# programmer.net
KiCad netlist of a schematic drawn in EAGLE
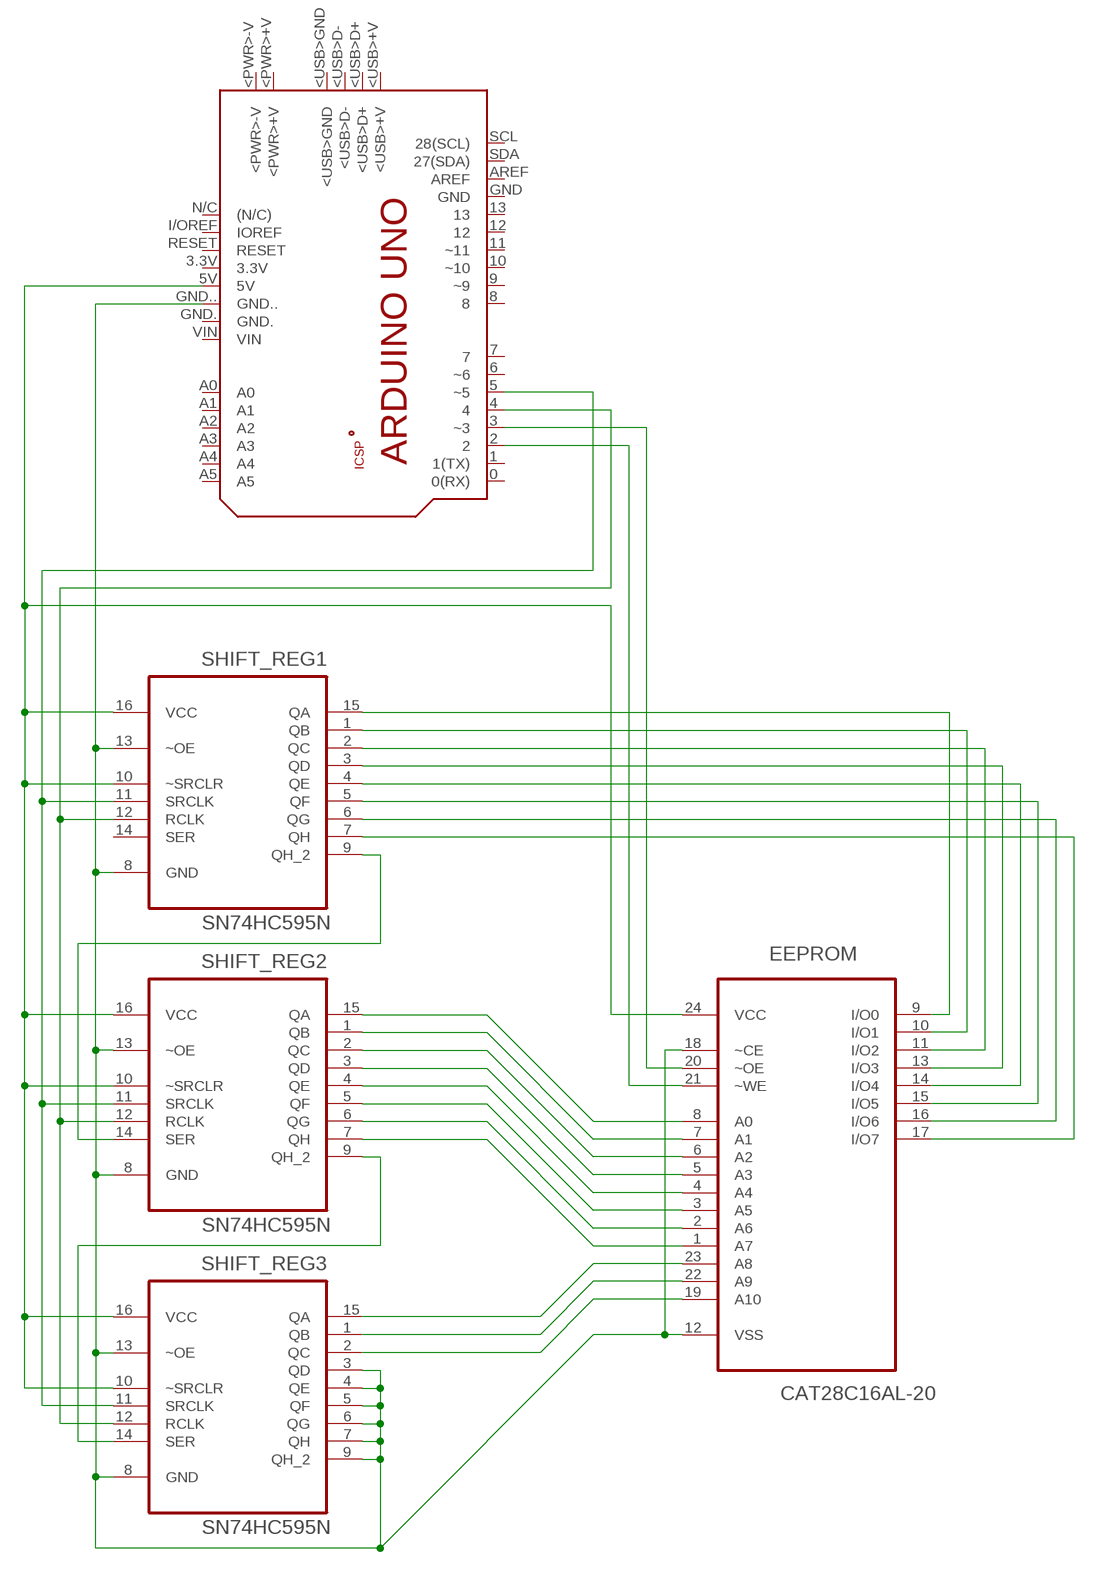
[diagram p0: schematic, sheet 1]

(export (version "E")
  (design (tool "Eeschema 10.0.6"))
  (components
    (comp (ref "EEPROM")
      (value "CAT28C16AL-20")
      (footprint "eagle-import:DIP254P1524X635-24")
      (libsource (lib "eagle-import") (part "CAT28C16AL-20"))
    )
    (comp (ref "MCU")
      (value "ARDUINO_UNO")
      (footprint "eagle-import:ARDUINO_UNO")
      (libsource (lib "eagle-import") (part "ARDUINO_UNO"))
    )
    (comp (ref "SHIFT_REG1")
      (value "SN74HC595N")
      (footprint "eagle-import:DIP254P762X508-16")
      (libsource (lib "eagle-import") (part "SN74HC595N"))
    )
    (comp (ref "SHIFT_REG2")
      (value "SN74HC595N")
      (footprint "eagle-import:DIP254P762X508-16")
      (libsource (lib "eagle-import") (part "SN74HC595N"))
    )
    (comp (ref "SHIFT_REG3")
      (value "SN74HC595N")
      (footprint "eagle-import:DIP254P762X508-16")
      (libsource (lib "eagle-import") (part "SN74HC595N"))
    )
  )
  (nets
    (net (code "1") (name "Net-(EEPROM-A0)") (class "Default")
      (node (ref "EEPROM") (pin "8") (pinfunction "A0_8") (pintype "input"))
      (node (ref "SHIFT_REG2") (pin "15") (pinfunction "QA_15") (pintype "output"))
    )
    (net (code "2") (name "Net-(EEPROM-A1)") (class "Default")
      (node (ref "EEPROM") (pin "7") (pinfunction "A1_7") (pintype "input"))
      (node (ref "SHIFT_REG2") (pin "1") (pinfunction "QB_1") (pintype "output"))
    )
    (net (code "3") (name "Net-(EEPROM-A2)") (class "Default")
      (node (ref "EEPROM") (pin "6") (pinfunction "A2_6") (pintype "input"))
      (node (ref "SHIFT_REG2") (pin "2") (pinfunction "QC_2") (pintype "output"))
    )
    (net (code "4") (name "Net-(EEPROM-A3)") (class "Default")
      (node (ref "EEPROM") (pin "5") (pinfunction "A3_5") (pintype "input"))
      (node (ref "SHIFT_REG2") (pin "3") (pinfunction "QD_3") (pintype "output"))
    )
    (net (code "5") (name "Net-(EEPROM-A4)") (class "Default")
      (node (ref "EEPROM") (pin "4") (pinfunction "A4_4") (pintype "input"))
      (node (ref "SHIFT_REG2") (pin "4") (pinfunction "QE_4") (pintype "output"))
    )
    (net (code "6") (name "Net-(EEPROM-A5)") (class "Default")
      (node (ref "EEPROM") (pin "3") (pinfunction "A5_3") (pintype "input"))
      (node (ref "SHIFT_REG2") (pin "5") (pinfunction "QF_5") (pintype "output"))
    )
    (net (code "7") (name "Net-(EEPROM-A6)") (class "Default")
      (node (ref "EEPROM") (pin "2") (pinfunction "A6_2") (pintype "input"))
      (node (ref "SHIFT_REG2") (pin "6") (pinfunction "QG_6") (pintype "output"))
    )
    (net (code "8") (name "Net-(EEPROM-A7)") (class "Default")
      (node (ref "EEPROM") (pin "1") (pinfunction "A7_1") (pintype "input"))
      (node (ref "SHIFT_REG2") (pin "7") (pinfunction "QH_7") (pintype "output"))
    )
    (net (code "9") (name "Net-(EEPROM-A8)") (class "Default")
      (node (ref "EEPROM") (pin "23") (pinfunction "A8_23") (pintype "input"))
      (node (ref "SHIFT_REG3") (pin "15") (pinfunction "QA_15") (pintype "output"))
    )
    (net (code "10") (name "Net-(EEPROM-A9)") (class "Default")
      (node (ref "EEPROM") (pin "22") (pinfunction "A9_22") (pintype "input"))
      (node (ref "SHIFT_REG3") (pin "1") (pinfunction "QB_1") (pintype "output"))
    )
    (net (code "11") (name "Net-(EEPROM-A10)") (class "Default")
      (node (ref "EEPROM") (pin "19") (pinfunction "A10_19") (pintype "input"))
      (node (ref "SHIFT_REG3") (pin "2") (pinfunction "QC_2") (pintype "output"))
    )
    (net (code "12") (name "Net-(EEPROM-I{slash}O0)") (class "Default")
      (node (ref "EEPROM") (pin "9") (pinfunction "I/O0_9") (pintype "bidirectional"))
      (node (ref "SHIFT_REG1") (pin "15") (pinfunction "QA_15") (pintype "output"))
    )
    (net (code "13") (name "Net-(EEPROM-I{slash}O1)") (class "Default")
      (node (ref "EEPROM") (pin "10") (pinfunction "I/O1_10") (pintype "bidirectional"))
      (node (ref "SHIFT_REG1") (pin "1") (pinfunction "QB_1") (pintype "output"))
    )
    (net (code "14") (name "Net-(EEPROM-I{slash}O2)") (class "Default")
      (node (ref "EEPROM") (pin "11") (pinfunction "I/O2_11") (pintype "bidirectional"))
      (node (ref "SHIFT_REG1") (pin "2") (pinfunction "QC_2") (pintype "output"))
    )
    (net (code "15") (name "Net-(EEPROM-I{slash}O3)") (class "Default")
      (node (ref "EEPROM") (pin "13") (pinfunction "I/O3_13") (pintype "bidirectional"))
      (node (ref "SHIFT_REG1") (pin "3") (pinfunction "QD_3") (pintype "output"))
    )
    (net (code "16") (name "Net-(EEPROM-I{slash}O4)") (class "Default")
      (node (ref "EEPROM") (pin "14") (pinfunction "I/O4_14") (pintype "bidirectional"))
      (node (ref "SHIFT_REG1") (pin "4") (pinfunction "QE_4") (pintype "output"))
    )
    (net (code "17") (name "Net-(EEPROM-I{slash}O5)") (class "Default")
      (node (ref "EEPROM") (pin "15") (pinfunction "I/O5_15") (pintype "bidirectional"))
      (node (ref "SHIFT_REG1") (pin "5") (pinfunction "QF_5") (pintype "output"))
    )
    (net (code "18") (name "Net-(EEPROM-I{slash}O6)") (class "Default")
      (node (ref "EEPROM") (pin "16") (pinfunction "I/O6_16") (pintype "bidirectional"))
      (node (ref "SHIFT_REG1") (pin "6") (pinfunction "QG_6") (pintype "output"))
    )
    (net (code "19") (name "Net-(EEPROM-I{slash}O7)") (class "Default")
      (node (ref "EEPROM") (pin "17") (pinfunction "I/O7_17") (pintype "bidirectional"))
      (node (ref "SHIFT_REG1") (pin "7") (pinfunction "QH_7") (pintype "output"))
    )
    (net (code "20") (name "Net-(EEPROM-VCC)") (class "Default")
      (node (ref "EEPROM") (pin "24") (pinfunction "VCC_24") (pintype "power_in"))
      (node (ref "MCU") (pin "5V") (pinfunction "5V_5V") (pintype "bidirectional"))
      (node (ref "SHIFT_REG1") (pin "10") (pinfunction "~{SRCLR}_10") (pintype "input"))
      (node (ref "SHIFT_REG1") (pin "16") (pinfunction "VCC_16") (pintype "power_in"))
      (node (ref "SHIFT_REG2") (pin "10") (pinfunction "~{SRCLR}_10") (pintype "input"))
      (node (ref "SHIFT_REG2") (pin "16") (pinfunction "VCC_16") (pintype "power_in"))
      (node (ref "SHIFT_REG3") (pin "10") (pinfunction "~{SRCLR}_10") (pintype "input"))
      (node (ref "SHIFT_REG3") (pin "16") (pinfunction "VCC_16") (pintype "power_in"))
    )
    (net (code "21") (name "Net-(EEPROM-VSS)") (class "Default")
      (node (ref "EEPROM") (pin "12") (pinfunction "VSS_12") (pintype "power_in"))
      (node (ref "EEPROM") (pin "18") (pinfunction "~{CE}_18") (pintype "input"))
      (node (ref "MCU") (pin "GND..") (pinfunction "GND.._GND..") (pintype "bidirectional"))
      (node (ref "SHIFT_REG1") (pin "13") (pinfunction "~{OE}_13") (pintype "input"))
      (node (ref "SHIFT_REG1") (pin "8") (pinfunction "GND_8") (pintype "passive"))
      (node (ref "SHIFT_REG2") (pin "13") (pinfunction "~{OE}_13") (pintype "input"))
      (node (ref "SHIFT_REG2") (pin "8") (pinfunction "GND_8") (pintype "passive"))
      (node (ref "SHIFT_REG3") (pin "13") (pinfunction "~{OE}_13") (pintype "input"))
      (node (ref "SHIFT_REG3") (pin "3") (pinfunction "QD_3") (pintype "output"))
      (node (ref "SHIFT_REG3") (pin "4") (pinfunction "QE_4") (pintype "output"))
      (node (ref "SHIFT_REG3") (pin "5") (pinfunction "QF_5") (pintype "output"))
      (node (ref "SHIFT_REG3") (pin "6") (pinfunction "QG_6") (pintype "output"))
      (node (ref "SHIFT_REG3") (pin "7") (pinfunction "QH_7") (pintype "output"))
      (node (ref "SHIFT_REG3") (pin "8") (pinfunction "GND_8") (pintype "passive"))
      (node (ref "SHIFT_REG3") (pin "9") (pinfunction "QH_2_9") (pintype "output"))
    )
    (net (code "22") (name "Net-(EEPROM-~{OE})") (class "Default")
      (node (ref "EEPROM") (pin "20") (pinfunction "~{OE}_20") (pintype "input"))
      (node (ref "MCU") (pin "3") (pinfunction "~{3}_3") (pintype "bidirectional"))
    )
    (net (code "23") (name "Net-(EEPROM-~{WE})") (class "Default")
      (node (ref "EEPROM") (pin "21") (pinfunction "~{WE}_21") (pintype "input"))
      (node (ref "MCU") (pin "2") (pinfunction "2_2") (pintype "bidirectional"))
    )
    (net (code "24") (name "Net-(MCU-~{5})") (class "Default")
      (node (ref "MCU") (pin "5") (pinfunction "~{5}_5") (pintype "bidirectional"))
      (node (ref "SHIFT_REG1") (pin "11") (pinfunction "SRCLK_11") (pintype "input"))
      (node (ref "SHIFT_REG2") (pin "11") (pinfunction "SRCLK_11") (pintype "input"))
      (node (ref "SHIFT_REG3") (pin "11") (pinfunction "SRCLK_11") (pintype "input"))
    )
    (net (code "25") (name "Net-(SHIFT_REG1-QH_2)") (class "Default")
      (node (ref "SHIFT_REG1") (pin "9") (pinfunction "QH_2_9") (pintype "output"))
      (node (ref "SHIFT_REG2") (pin "14") (pinfunction "SER_14") (pintype "input"))
    )
    (net (code "26") (name "Net-(SHIFT_REG1-RCLK)") (class "Default")
      (node (ref "MCU") (pin "4") (pinfunction "4_4") (pintype "bidirectional"))
      (node (ref "SHIFT_REG1") (pin "12") (pinfunction "RCLK_12") (pintype "input"))
      (node (ref "SHIFT_REG2") (pin "12") (pinfunction "RCLK_12") (pintype "input"))
      (node (ref "SHIFT_REG3") (pin "12") (pinfunction "RCLK_12") (pintype "input"))
    )
    (net (code "27") (name "Net-(SHIFT_REG2-QH_2)") (class "Default")
      (node (ref "SHIFT_REG2") (pin "9") (pinfunction "QH_2_9") (pintype "output"))
      (node (ref "SHIFT_REG3") (pin "14") (pinfunction "SER_14") (pintype "input"))
    )
    (net (code "28") (name "unconnected-(MCU-(N{slash}C)-PadN{slash}C)") (class "Default")
      (node (ref "MCU") (pin "N/C") (pinfunction "(N/C)_N/C") (pintype "bidirectional"))
    )
    (net (code "29") (name "unconnected-(MCU-0(RX)-Pad0)") (class "Default")
      (node (ref "MCU") (pin "0") (pinfunction "0(RX)_0") (pintype "bidirectional"))
    )
    (net (code "30") (name "unconnected-(MCU-1(TX)-Pad1)") (class "Default")
      (node (ref "MCU") (pin "1") (pinfunction "1(TX)_1") (pintype "bidirectional"))
    )
    (net (code "31") (name "unconnected-(MCU-27(SDA)-PadSDA)") (class "Default")
      (node (ref "MCU") (pin "SDA") (pinfunction "27(SDA)_SDA") (pintype "bidirectional"))
    )
    (net (code "32") (name "unconnected-(MCU-28(SCL)-PadSCL)") (class "Default")
      (node (ref "MCU") (pin "SCL") (pinfunction "28(SCL)_SCL") (pintype "bidirectional"))
    )
    (net (code "33") (name "unconnected-(MCU-IOREF-PadI{slash}OREF)") (class "Default")
      (node (ref "MCU") (pin "I/OREF") (pinfunction "IOREF_I/OREF") (pintype "bidirectional"))
    )
    (net (code "34") (name "unconnected-(MCU-Pad+5V)") (class "Default")
      (node (ref "MCU") (pin "+5V") (pinfunction "+5V_+5V") (pintype "bidirectional"))
    )
    (net (code "35") (name "unconnected-(MCU-Pad3.3V)") (class "Default")
      (node (ref "MCU") (pin "3.3V") (pinfunction "3.3V_3.3V") (pintype "bidirectional"))
    )
    (net (code "36") (name "unconnected-(MCU-Pad7)") (class "Default")
      (node (ref "MCU") (pin "7") (pinfunction "7_7") (pintype "bidirectional"))
    )
    (net (code "37") (name "unconnected-(MCU-Pad8)") (class "Default")
      (node (ref "MCU") (pin "8") (pinfunction "8_8") (pintype "bidirectional"))
    )
    (net (code "38") (name "unconnected-(MCU-Pad12)") (class "Default")
      (node (ref "MCU") (pin "12") (pinfunction "12_12") (pintype "bidirectional"))
    )
    (net (code "39") (name "unconnected-(MCU-Pad13)") (class "Default")
      (node (ref "MCU") (pin "13") (pinfunction "13_13") (pintype "bidirectional"))
    )
    (net (code "40") (name "unconnected-(MCU-Pad<PWR>+V)") (class "Default")
      (node (ref "MCU") (pin "<PWR>+V") (pinfunction "<PWR>+V_<PWR>+V") (pintype "bidirectional"))
    )
    (net (code "41") (name "unconnected-(MCU-Pad<PWR>-V)") (class "Default")
      (node (ref "MCU") (pin "<PWR>-V") (pinfunction "<PWR>-V_<PWR>-V") (pintype "bidirectional"))
    )
    (net (code "42") (name "unconnected-(MCU-Pad<USB>+V)") (class "Default")
      (node (ref "MCU") (pin "<USB>+V") (pinfunction "<USB>+V_<USB>+V") (pintype "bidirectional"))
    )
    (net (code "43") (name "unconnected-(MCU-Pad<USB>D+)") (class "Default")
      (node (ref "MCU") (pin "<USB>D+") (pinfunction "<USB>D+_<USB>D+") (pintype "bidirectional"))
    )
    (net (code "44") (name "unconnected-(MCU-Pad<USB>D-)") (class "Default")
      (node (ref "MCU") (pin "<USB>D-") (pinfunction "<USB>D-_<USB>D-") (pintype "bidirectional"))
    )
    (net (code "45") (name "unconnected-(MCU-Pad<USB>GND)") (class "Default")
      (node (ref "MCU") (pin "<USB>GND") (pinfunction "<USB>GND_<USB>GND") (pintype "bidirectional"))
    )
    (net (code "46") (name "unconnected-(MCU-PadA0)") (class "Default")
      (node (ref "MCU") (pin "A0") (pinfunction "A0_A0") (pintype "bidirectional"))
    )
    (net (code "47") (name "unconnected-(MCU-PadA1)") (class "Default")
      (node (ref "MCU") (pin "A1") (pinfunction "A1_A1") (pintype "bidirectional"))
    )
    (net (code "48") (name "unconnected-(MCU-PadA2)") (class "Default")
      (node (ref "MCU") (pin "A2") (pinfunction "A2_A2") (pintype "bidirectional"))
    )
    (net (code "49") (name "unconnected-(MCU-PadA3)") (class "Default")
      (node (ref "MCU") (pin "A3") (pinfunction "A3_A3") (pintype "bidirectional"))
    )
    (net (code "50") (name "unconnected-(MCU-PadA4)") (class "Default")
      (node (ref "MCU") (pin "A4") (pinfunction "A4_A4") (pintype "bidirectional"))
    )
    (net (code "51") (name "unconnected-(MCU-PadA5)") (class "Default")
      (node (ref "MCU") (pin "A5") (pinfunction "A5_A5") (pintype "bidirectional"))
    )
    (net (code "52") (name "unconnected-(MCU-PadAREF)") (class "Default")
      (node (ref "MCU") (pin "AREF") (pinfunction "AREF_AREF") (pintype "bidirectional"))
    )
    (net (code "53") (name "unconnected-(MCU-PadGND)") (class "Default")
      (node (ref "MCU") (pin "GND") (pinfunction "GND_GND") (pintype "bidirectional"))
    )
    (net (code "54") (name "unconnected-(MCU-PadGND.)") (class "Default")
      (node (ref "MCU") (pin "GND.") (pinfunction "GND._GND.") (pintype "bidirectional"))
    )
    (net (code "55") (name "unconnected-(MCU-PadGND_)") (class "Default")
      (node (ref "MCU") (pin "GND_") (pinfunction "GND__GND_") (pintype "bidirectional"))
    )
    (net (code "56") (name "unconnected-(MCU-PadMISO)") (class "Default")
      (node (ref "MCU") (pin "MISO") (pinfunction "MISO_MISO") (pintype "bidirectional"))
    )
    (net (code "57") (name "unconnected-(MCU-PadMOSI)") (class "Default")
      (node (ref "MCU") (pin "MOSI") (pinfunction "MOSI_MOSI") (pintype "bidirectional"))
    )
    (net (code "58") (name "unconnected-(MCU-PadRESET)") (class "Default")
      (node (ref "MCU") (pin "RESET") (pinfunction "RESET_RESET") (pintype "bidirectional"))
    )
    (net (code "59") (name "unconnected-(MCU-PadRESET.)") (class "Default")
      (node (ref "MCU") (pin "RESET.") (pinfunction "RESET._RESET.") (pintype "bidirectional"))
    )
    (net (code "60") (name "unconnected-(MCU-PadSCK)") (class "Default")
      (node (ref "MCU") (pin "SCK") (pinfunction "SCK_SCK") (pintype "bidirectional"))
    )
    (net (code "61") (name "unconnected-(MCU-PadVIN)") (class "Default")
      (node (ref "MCU") (pin "VIN") (pinfunction "VIN_VIN") (pintype "bidirectional"))
    )
    (net (code "62") (name "unconnected-(MCU-~{6}-Pad6)") (class "Default")
      (node (ref "MCU") (pin "6") (pinfunction "~{6}_6") (pintype "bidirectional"))
    )
    (net (code "63") (name "unconnected-(MCU-~{9}-Pad9)") (class "Default")
      (node (ref "MCU") (pin "9") (pinfunction "~{9}_9") (pintype "bidirectional"))
    )
    (net (code "64") (name "unconnected-(MCU-~{10}-Pad10)") (class "Default")
      (node (ref "MCU") (pin "10") (pinfunction "~{10}_10") (pintype "bidirectional"))
    )
    (net (code "65") (name "unconnected-(MCU-~{11}-Pad11)") (class "Default")
      (node (ref "MCU") (pin "11") (pinfunction "~{11}_11") (pintype "bidirectional"))
    )
    (net (code "66") (name "unconnected-(SHIFT_REG1-SER-Pad14)") (class "Default")
      (node (ref "SHIFT_REG1") (pin "14") (pinfunction "SER_14") (pintype "input"))
    )
  )
)
